# eggDrop.net
KiCad netlist of a schematic drawn in EAGLE
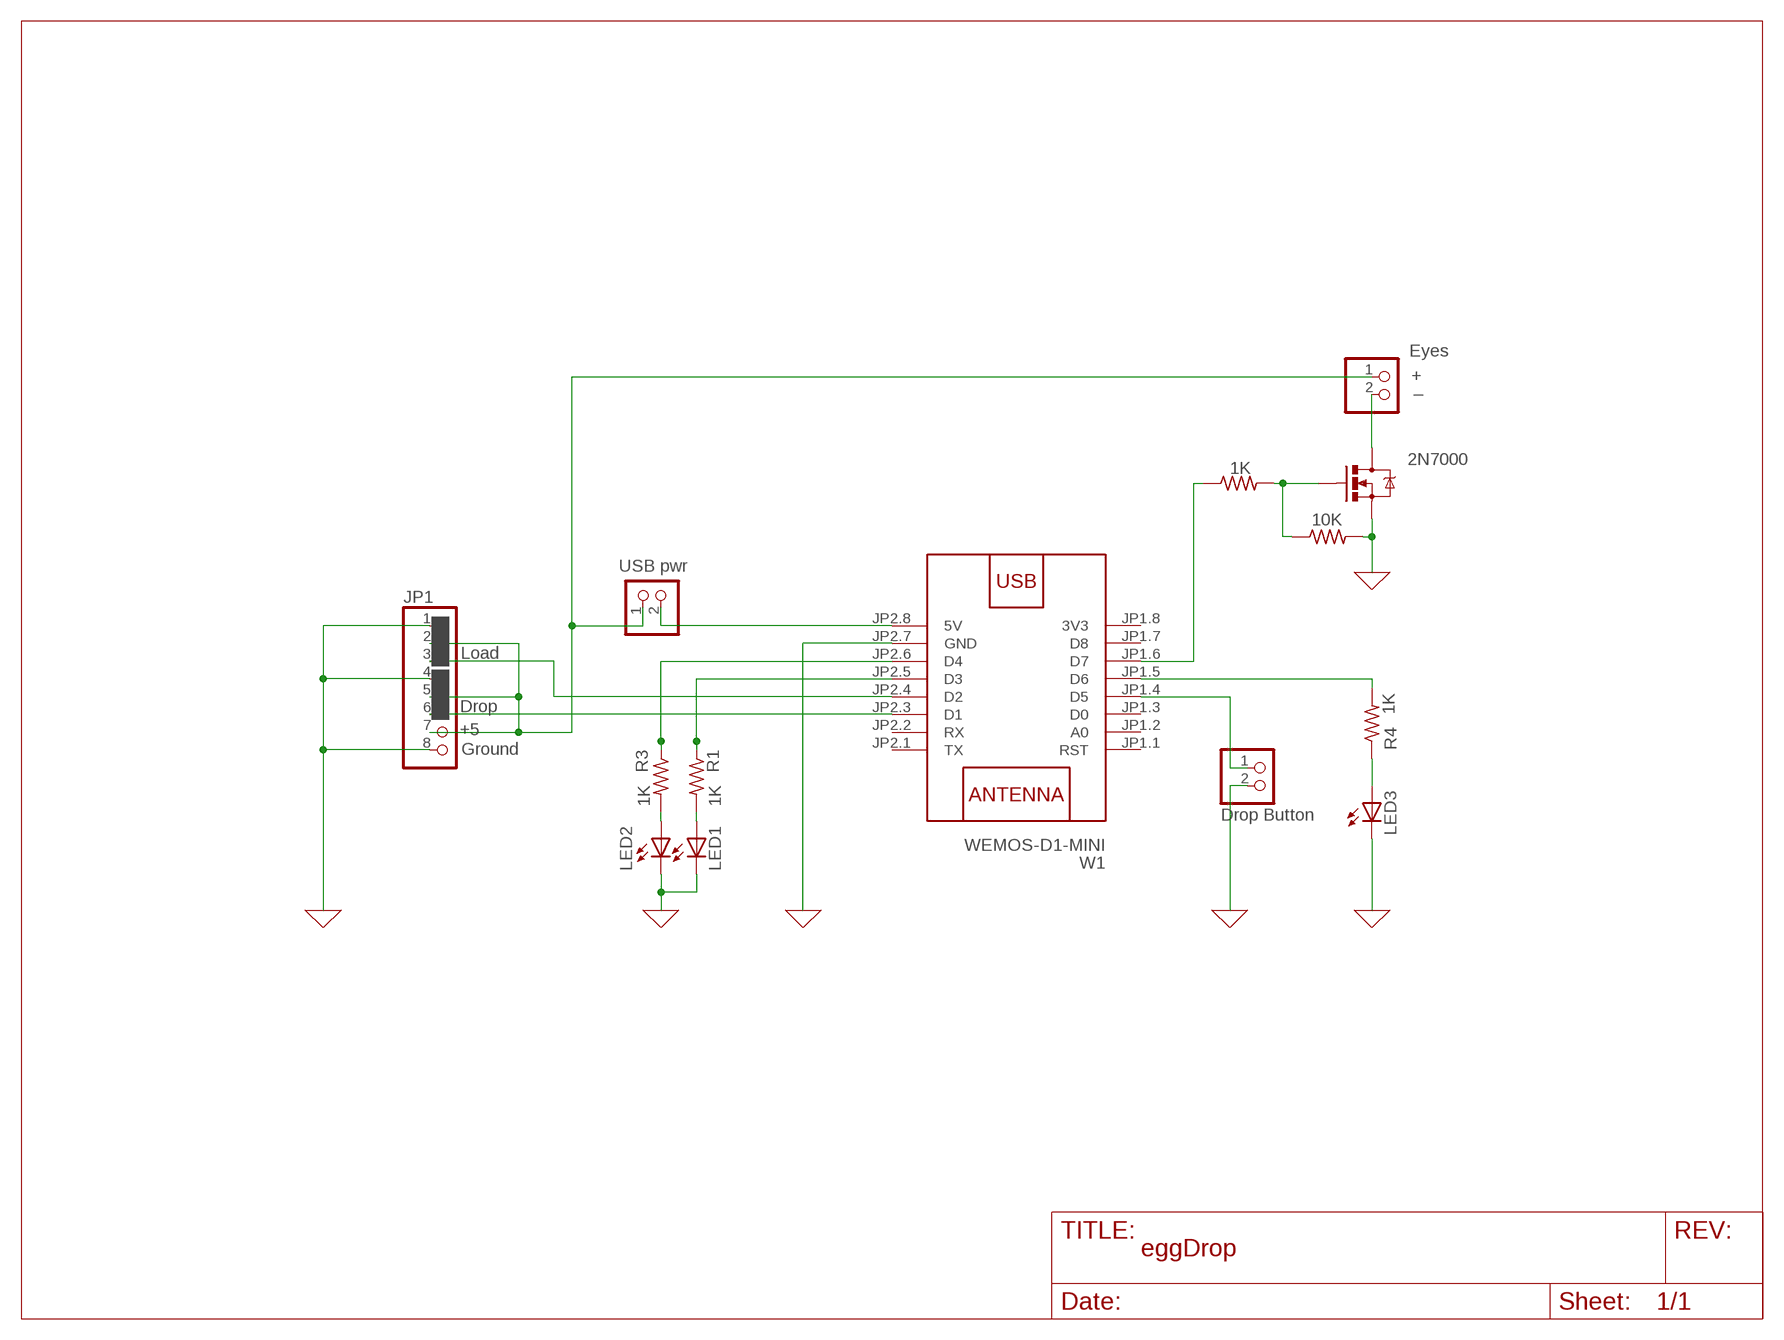
[diagram p0: schematic, sheet 1]

(export (version "E")
  (design (tool "Eeschema 10.0.6"))
  (components
    (comp (ref "2N7000")
      (value "MOSFET-NCHANNEL2N7000")
      (footprint "eagle-import:TO-92")
      (libsource (lib "eagle-import") (part "MOSFET-NCHANNEL2N7000"))
    )
    (comp (ref "JP1")
      (value "PINHD-1X8BIG")
      (footprint "eagle-import:1X08-BIG")
      (libsource (lib "eagle-import") (part "PINHD-1X8BIG"))
    )
    (comp (ref "JP2")
      (value "USB pwr")
      (footprint "eagle-import:1X02")
      (libsource (lib "eagle-import") (part "PINHD-1X2"))
    )
    (comp (ref "JP3")
      (value "Drop Button")
      (footprint "eagle-import:1X02")
      (libsource (lib "eagle-import") (part "PINHD-1X2"))
    )
    (comp (ref "JP4")
      (value "Eyes")
      (footprint "eagle-import:1X02")
      (libsource (lib "eagle-import") (part "PINHD-1X2"))
    )
    (comp (ref "LED1")
      (value "LED5MM")
      (footprint "eagle-import:LED5MM")
      (libsource (lib "eagle-import") (part "LED5MM"))
    )
    (comp (ref "LED2")
      (value "LED5MM")
      (footprint "eagle-import:LED5MM")
      (libsource (lib "eagle-import") (part "LED5MM"))
    )
    (comp (ref "LED3")
      (value "LED5MM")
      (footprint "eagle-import:LED5MM")
      (libsource (lib "eagle-import") (part "LED5MM"))
    )
    (comp (ref "R1")
      (value "1K")
      (footprint "eagle-import:0207_10")
      (libsource (lib "eagle-import") (part "R-US_0207/10"))
    )
    (comp (ref "R2")
      (value "10K")
      (footprint "eagle-import:0207_10")
      (libsource (lib "eagle-import") (part "R-US_0207/10"))
    )
    (comp (ref "R3")
      (value "1K")
      (footprint "eagle-import:0207_10")
      (libsource (lib "eagle-import") (part "R-US_0207/10"))
    )
    (comp (ref "R4")
      (value "1K")
      (footprint "eagle-import:0207_10")
      (libsource (lib "eagle-import") (part "R-US_0207/10"))
    )
    (comp (ref "R5")
      (value "1K")
      (footprint "eagle-import:0207_10")
      (libsource (lib "eagle-import") (part "R-US_0207/10"))
    )
    (comp (ref "W1")
      (value "WEMOS-D1-MINI")
      (footprint "eagle-import:WEMOS-D1-MINI")
      (libsource (lib "eagle-import") (part "WEMOS-D1-MINI"))
    )
  )
  (nets
    (net (code "1") (name "/3V3") (class "Default")
      (node (ref "W1") (pin "JP1.8") (pinfunction "3V3_JP1.8") (pintype "power_in"))
    )
    (net (code "2") (name "GND") (class "Default")
      (node (ref "2N7000") (pin "1") (pinfunction "S_1") (pintype "passive"))
      (node (ref "JP1") (pin "1") (pinfunction "1_1") (pintype "passive"))
      (node (ref "JP1") (pin "4") (pinfunction "4_4") (pintype "passive"))
      (node (ref "JP1") (pin "8") (pinfunction "8_8") (pintype "passive"))
      (node (ref "JP3") (pin "2") (pinfunction "2_2") (pintype "passive"))
      (node (ref "LED1") (pin "K") (pinfunction "C_K") (pintype "passive"))
      (node (ref "LED2") (pin "K") (pinfunction "C_K") (pintype "passive"))
      (node (ref "LED3") (pin "K") (pinfunction "C_K") (pintype "passive"))
      (node (ref "R2") (pin "2") (pinfunction "2_2") (pintype "passive"))
      (node (ref "W1") (pin "JP2.7") (pinfunction "GND_JP2.7") (pintype "power_in"))
    )
    (net (code "3") (name "Net-(2N7000-D)") (class "Default")
      (node (ref "2N7000") (pin "3") (pinfunction "D_3") (pintype "passive"))
      (node (ref "JP4") (pin "2") (pinfunction "2_2") (pintype "passive"))
    )
    (net (code "4") (name "Net-(2N7000-G)") (class "Default")
      (node (ref "2N7000") (pin "2") (pinfunction "G_2") (pintype "passive"))
      (node (ref "R2") (pin "1") (pinfunction "1_1") (pintype "passive"))
      (node (ref "R5") (pin "2") (pinfunction "2_2") (pintype "passive"))
    )
    (net (code "5") (name "Net-(JP1-Pad2)") (class "Default")
      (node (ref "JP1") (pin "2") (pinfunction "2_2") (pintype "passive"))
      (node (ref "JP1") (pin "5") (pinfunction "5_5") (pintype "passive"))
      (node (ref "JP1") (pin "7") (pinfunction "7_7") (pintype "passive"))
      (node (ref "JP2") (pin "1") (pinfunction "1_1") (pintype "passive"))
      (node (ref "JP4") (pin "1") (pinfunction "1_1") (pintype "passive"))
    )
    (net (code "6") (name "Net-(LED1-PadA)") (class "Default")
      (node (ref "LED1") (pin "A") (pinfunction "A_A") (pintype "passive"))
      (node (ref "R1") (pin "2") (pinfunction "2_2") (pintype "passive"))
    )
    (net (code "7") (name "Net-(LED2-PadA)") (class "Default")
      (node (ref "LED2") (pin "A") (pinfunction "A_A") (pintype "passive"))
      (node (ref "R3") (pin "2") (pinfunction "2_2") (pintype "passive"))
    )
    (net (code "8") (name "Net-(LED3-PadA)") (class "Default")
      (node (ref "LED3") (pin "A") (pinfunction "A_A") (pintype "passive"))
      (node (ref "R4") (pin "1") (pinfunction "1_1") (pintype "passive"))
    )
    (net (code "9") (name "Net-(W1-5V)") (class "Default")
      (node (ref "JP2") (pin "2") (pinfunction "2_2") (pintype "passive"))
      (node (ref "W1") (pin "JP2.8") (pinfunction "5V_JP2.8") (pintype "power_in"))
    )
    (net (code "10") (name "Net-(W1-D1)") (class "Default")
      (node (ref "JP1") (pin "6") (pinfunction "6_6") (pintype "passive"))
      (node (ref "W1") (pin "JP2.3") (pinfunction "D1_JP2.3") (pintype "bidirectional"))
    )
    (net (code "11") (name "Net-(W1-D2)") (class "Default")
      (node (ref "JP1") (pin "3") (pinfunction "3_3") (pintype "passive"))
      (node (ref "W1") (pin "JP2.4") (pinfunction "D2_JP2.4") (pintype "bidirectional"))
    )
    (net (code "12") (name "Net-(W1-D3)") (class "Default")
      (node (ref "R1") (pin "1") (pinfunction "1_1") (pintype "passive"))
      (node (ref "W1") (pin "JP2.5") (pinfunction "D3_JP2.5") (pintype "bidirectional"))
    )
    (net (code "13") (name "Net-(W1-D4)") (class "Default")
      (node (ref "R3") (pin "1") (pinfunction "1_1") (pintype "passive"))
      (node (ref "W1") (pin "JP2.6") (pinfunction "D4_JP2.6") (pintype "bidirectional"))
    )
    (net (code "14") (name "Net-(W1-D5)") (class "Default")
      (node (ref "JP3") (pin "1") (pinfunction "1_1") (pintype "passive"))
      (node (ref "W1") (pin "JP1.4") (pinfunction "D5_JP1.4") (pintype "bidirectional"))
    )
    (net (code "15") (name "Net-(W1-D6)") (class "Default")
      (node (ref "R4") (pin "2") (pinfunction "2_2") (pintype "passive"))
      (node (ref "W1") (pin "JP1.5") (pinfunction "D6_JP1.5") (pintype "bidirectional"))
    )
    (net (code "16") (name "Net-(W1-D7)") (class "Default")
      (node (ref "R5") (pin "1") (pinfunction "1_1") (pintype "passive"))
      (node (ref "W1") (pin "JP1.6") (pinfunction "D7_JP1.6") (pintype "bidirectional"))
    )
    (net (code "17") (name "unconnected-(W1-A0-PadJP1.2)") (class "Default")
      (node (ref "W1") (pin "JP1.2") (pinfunction "A0_JP1.2") (pintype "bidirectional"))
    )
    (net (code "18") (name "unconnected-(W1-D0-PadJP1.3)") (class "Default")
      (node (ref "W1") (pin "JP1.3") (pinfunction "D0_JP1.3") (pintype "bidirectional"))
    )
    (net (code "19") (name "unconnected-(W1-D8-PadJP1.7)") (class "Default")
      (node (ref "W1") (pin "JP1.7") (pinfunction "D8_JP1.7") (pintype "bidirectional"))
    )
    (net (code "20") (name "unconnected-(W1-RST-PadJP1.1)") (class "Default")
      (node (ref "W1") (pin "JP1.1") (pinfunction "RST_JP1.1") (pintype "bidirectional"))
    )
    (net (code "21") (name "unconnected-(W1-RX-PadJP2.2)") (class "Default")
      (node (ref "W1") (pin "JP2.2") (pinfunction "RX_JP2.2") (pintype "bidirectional"))
    )
    (net (code "22") (name "unconnected-(W1-TX-PadJP2.1)") (class "Default")
      (node (ref "W1") (pin "JP2.1") (pinfunction "TX_JP2.1") (pintype "bidirectional"))
    )
  )
)
